# PCB_Design_Circuit.net
KiCad netlist of a schematic drawn in EAGLE
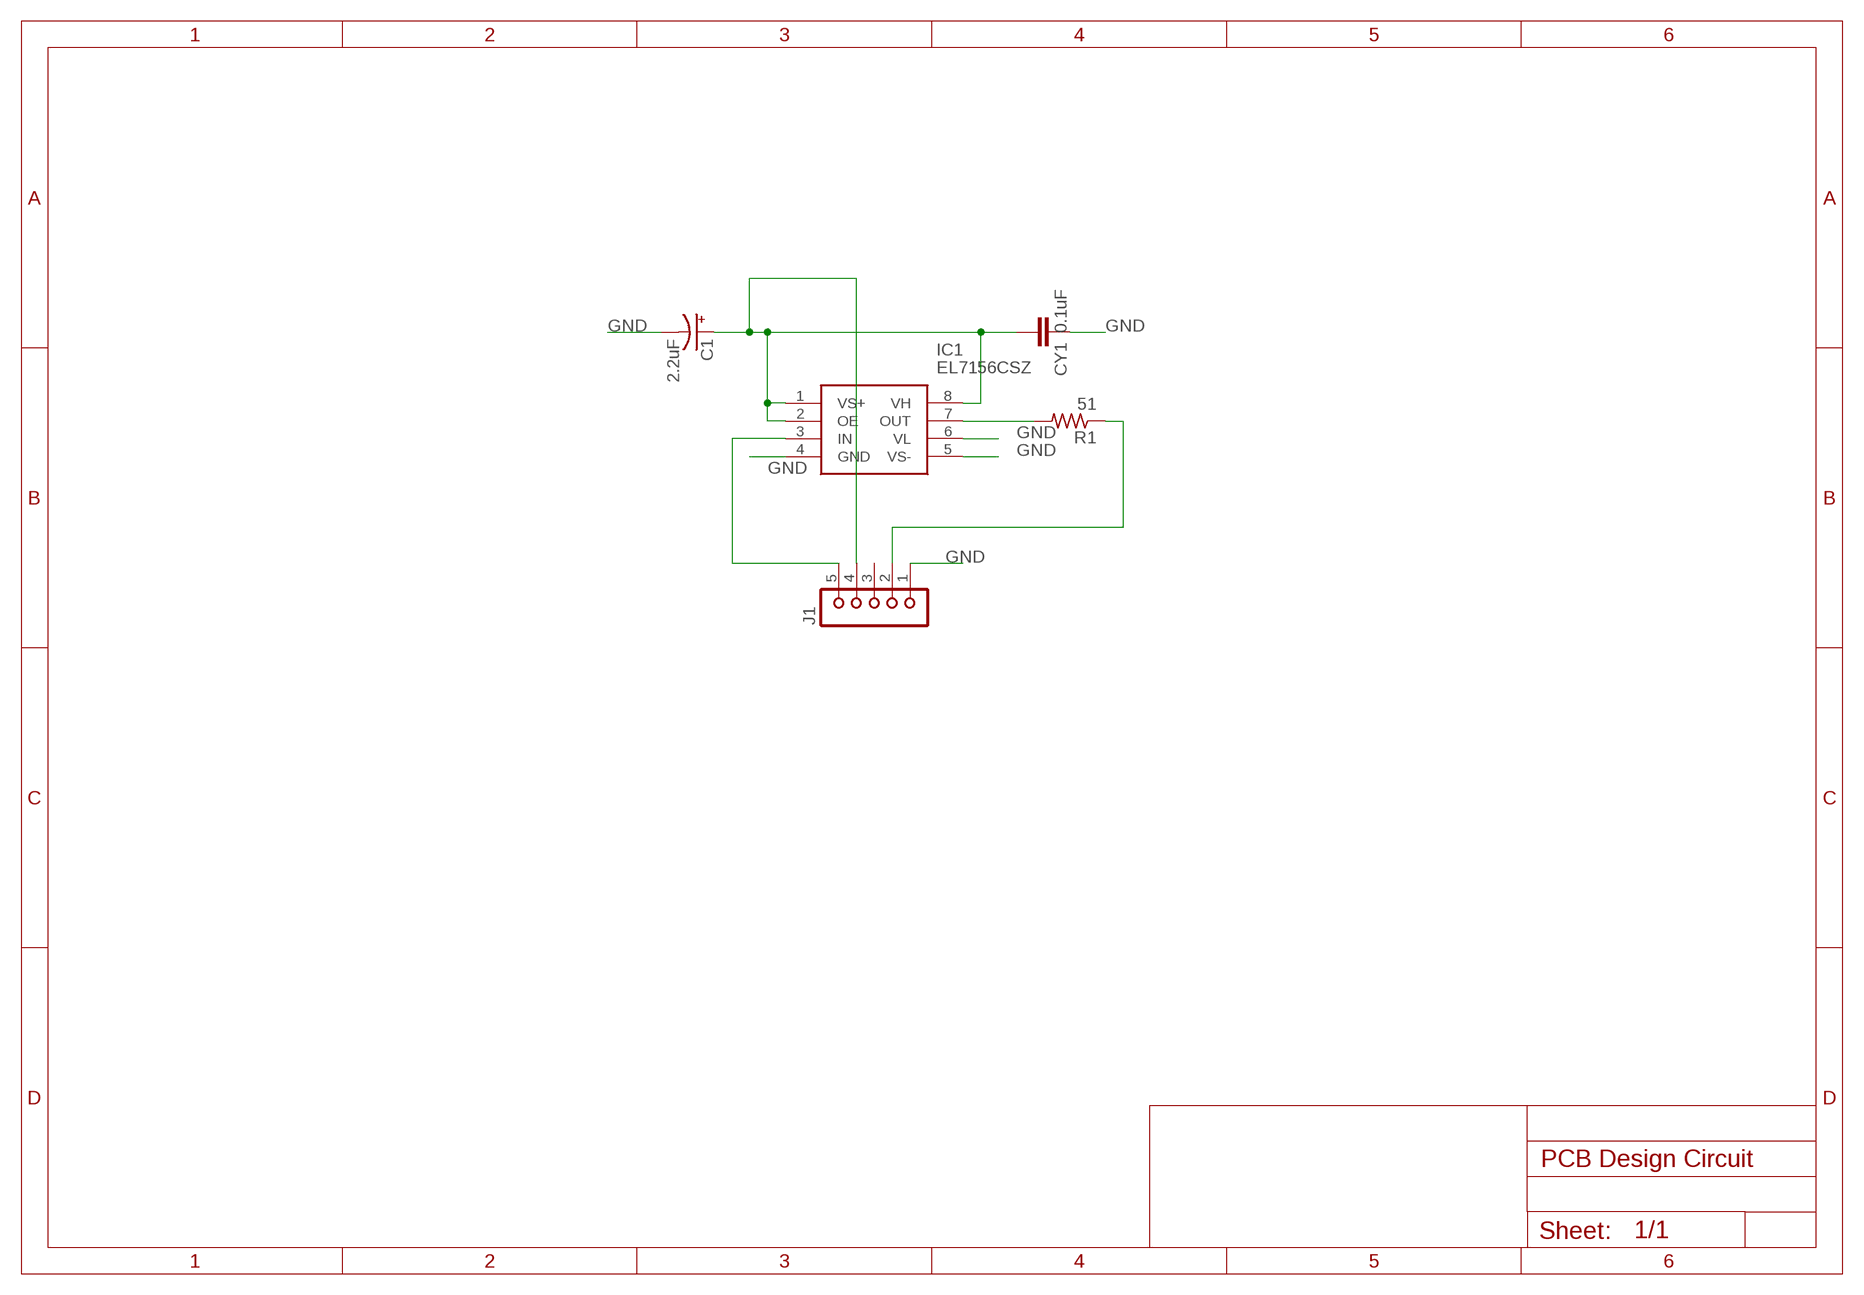
[diagram p0: schematic, sheet 1]

(export (version "E")
  (design (tool "Eeschema 10.0.6"))
  (components
    (comp (ref "C1")
      (value "2.2uF")
      (footprint "eagle-import:E2,5-6")
      (libsource (lib "eagle-import") (part "CPOL-USE2.5-6"))
    )
    (comp (ref "CY1")
      (value "0.1uF")
      (footprint "eagle-import:YC7B5")
      (libsource (lib "eagle-import") (part "CYYC7B5"))
    )
    (comp (ref "IC1")
      (value "EL7156CSZ")
      (footprint "eagle-import:SOIC127P599X173-8N")
      (fields (field (name "MOUSER_PART_NUMBER") "968-EL7156CSZ"))
      (libsource (lib "eagle-import") (part "EL7156CSZ"))
    )
    (comp (ref "J1")
      (value "JU05")
      (footprint "eagle-import:JU05")
      (libsource (lib "eagle-import") (part "JU05"))
    )
    (comp (ref "R1")
      (value "51")
      (footprint "eagle-import:0207_7")
      (libsource (lib "eagle-import") (part "R-US_0207/7"))
    )
  )
  (nets
    (net (code "1") (name "/GND") (class "Default")
      (node (ref "C1") (pin "-") (pinfunction "-_-") (pintype "passive"))
      (node (ref "CY1") (pin "1") (pinfunction "1_1") (pintype "passive"))
      (node (ref "IC1") (pin "4") (pinfunction "GND_4") (pintype "bidirectional"))
      (node (ref "IC1") (pin "5") (pinfunction "VS-_5") (pintype "bidirectional"))
      (node (ref "IC1") (pin "6") (pinfunction "VL_6") (pintype "bidirectional"))
      (node (ref "J1") (pin "1") (pinfunction "1_1") (pintype "passive"))
    )
    (net (code "2") (name "Net-(IC1-IN)") (class "Default")
      (node (ref "IC1") (pin "3") (pinfunction "IN_3") (pintype "bidirectional"))
      (node (ref "J1") (pin "5") (pinfunction "5_5") (pintype "passive"))
    )
    (net (code "3") (name "Net-(IC1-OE)") (class "Default")
      (node (ref "C1") (pin "+") (pinfunction "+_+") (pintype "passive"))
      (node (ref "CY1") (pin "2") (pinfunction "2_2") (pintype "passive"))
      (node (ref "IC1") (pin "1") (pinfunction "VS+_1") (pintype "bidirectional"))
      (node (ref "IC1") (pin "2") (pinfunction "OE_2") (pintype "bidirectional"))
      (node (ref "IC1") (pin "8") (pinfunction "VH_8") (pintype "bidirectional"))
      (node (ref "J1") (pin "4") (pinfunction "4_4") (pintype "passive"))
    )
    (net (code "4") (name "Net-(IC1-OUT)") (class "Default")
      (node (ref "IC1") (pin "7") (pinfunction "OUT_7") (pintype "bidirectional"))
      (node (ref "R1") (pin "2") (pinfunction "2_2") (pintype "passive"))
    )
    (net (code "5") (name "Net-(J1-Pad2)") (class "Default")
      (node (ref "J1") (pin "2") (pinfunction "2_2") (pintype "passive"))
      (node (ref "R1") (pin "1") (pinfunction "1_1") (pintype "passive"))
    )
    (net (code "6") (name "unconnected-(J1-Pad3)") (class "Default")
      (node (ref "J1") (pin "3") (pinfunction "3_3") (pintype "passive"))
    )
  )
)
